# Core.net
KiCad netlist of a schematic drawn in Altium Designer
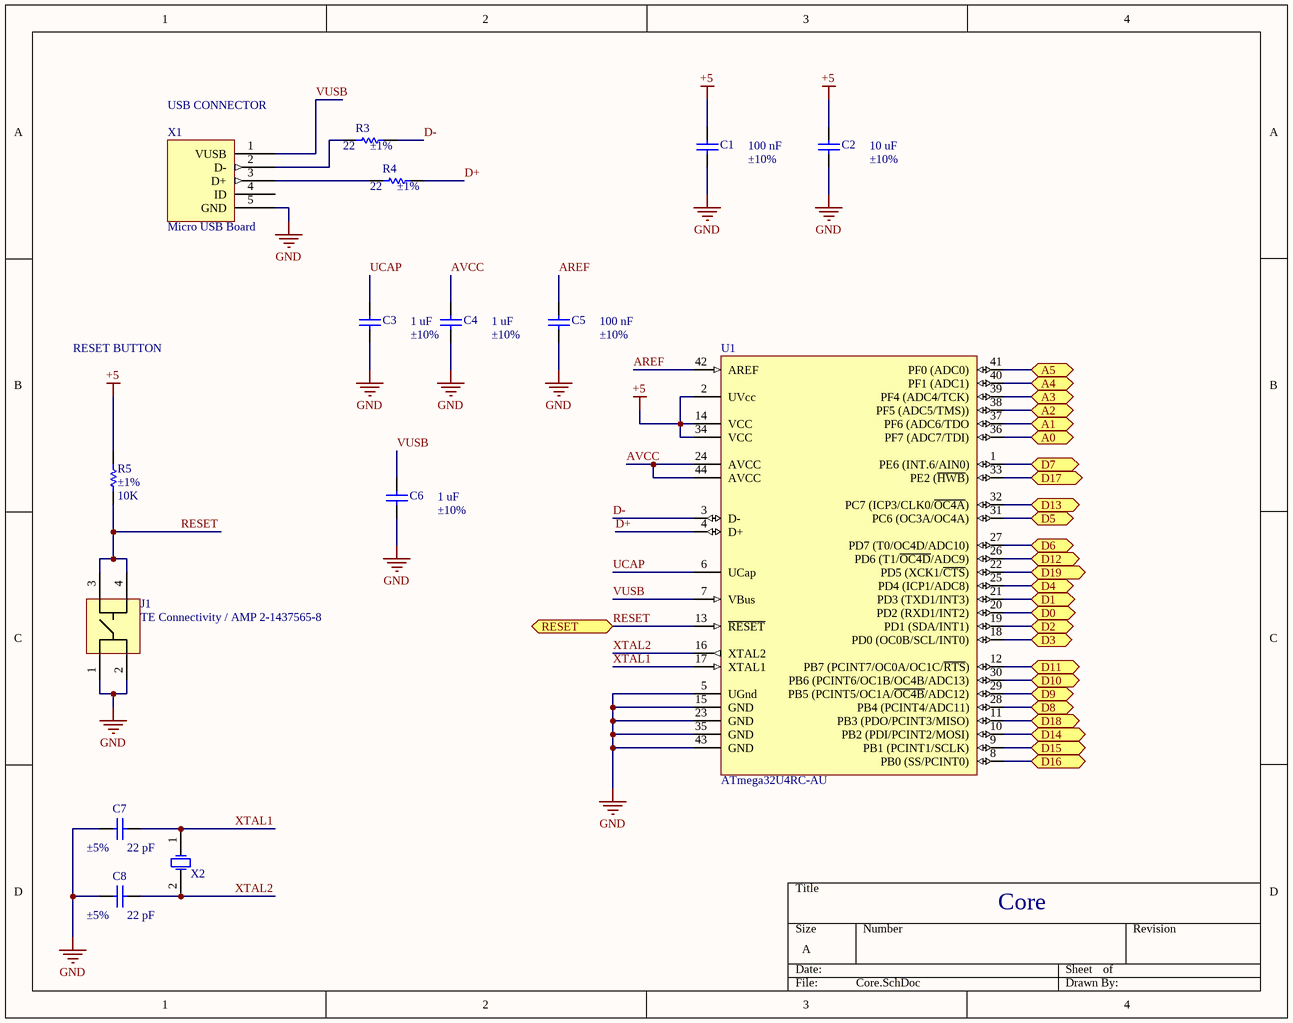
[diagram p0: Core.SchDoc]

(export (version "E")
  (design (tool "Eeschema 10.0.6"))
  (components
    (comp (ref "C1")
      (value "Taiyo Yuden LMK212BJ106KG-T")
      (footprint "PCB-i747o4qnz4fc2aqkwc14-1")
      (description "Cap Ceramic 10uF 10V X5R 10% SMD 0805 85?C T/R")
      (fields
        (field (name "MANUFACTURER PART NUMBER") "LMK212BJ106KG-T")
        (field (name "CAPACITANCE") "100 nF")
        (field (name "CAPACITANCE TOLERANCE") "±10%")
      )
      (libsource (lib "CommunityVault") (part "CMP-6ecba7c24c09b10c-2"))
    )
    (comp (ref "C2")
      (value "Taiyo Yuden LMK212BJ106KG-T")
      (footprint "PCB-i747o4qnz4fc2aqkwc14-1")
      (description "Cap Ceramic 10uF 10V X5R 10% SMD 0805 85?C T/R")
      (fields
        (field (name "MANUFACTURER PART NUMBER") "LMK212BJ106KG-T")
        (field (name "CAPACITANCE") "10 uF")
        (field (name "CAPACITANCE TOLERANCE") "±10%")
      )
      (libsource (lib "CommunityVault") (part "CMP-6ecba7c24c09b10c-2"))
    )
    (comp (ref "C3")
      (value "Taiyo Yuden LMK212BJ106KG-T")
      (footprint "PCB-i747o4qnz4fc2aqkwc14-1")
      (description "Cap Ceramic 10uF 10V X5R 10% SMD 0805 85?C T/R")
      (fields
        (field (name "MANUFACTURER PART NUMBER") "LMK212BJ106KG-T")
        (field (name "CAPACITANCE") "1 uF")
        (field (name "CAPACITANCE TOLERANCE") "±10%")
      )
      (libsource (lib "CommunityVault") (part "CMP-6ecba7c24c09b10c-2"))
    )
    (comp (ref "C4")
      (value "Taiyo Yuden LMK212BJ106KG-T")
      (footprint "PCB-i747o4qnz4fc2aqkwc14-1")
      (description "Cap Ceramic 10uF 10V X5R 10% SMD 0805 85?C T/R")
      (fields
        (field (name "MANUFACTURER PART NUMBER") "LMK212BJ106KG-T")
        (field (name "CAPACITANCE") "1 uF")
        (field (name "CAPACITANCE TOLERANCE") "±10%")
      )
      (libsource (lib "CommunityVault") (part "CMP-6ecba7c24c09b10c-2"))
    )
    (comp (ref "C5")
      (value "Taiyo Yuden LMK212BJ106KG-T")
      (footprint "PCB-i747o4qnz4fc2aqkwc14-1")
      (description "Cap Ceramic 10uF 10V X5R 10% SMD 0805 85?C T/R")
      (fields
        (field (name "MANUFACTURER PART NUMBER") "LMK212BJ106KG-T")
        (field (name "CAPACITANCE") "100 nF")
        (field (name "CAPACITANCE TOLERANCE") "±10%")
      )
      (libsource (lib "CommunityVault") (part "CMP-6ecba7c24c09b10c-2"))
    )
    (comp (ref "C6")
      (value "Taiyo Yuden LMK212BJ106KG-T")
      (footprint "PCB-i747o4qnz4fc2aqkwc14-1")
      (description "Cap Ceramic 10uF 10V X5R 10% SMD 0805 85?C T/R")
      (fields
        (field (name "MANUFACTURER PART NUMBER") "LMK212BJ106KG-T")
        (field (name "CAPACITANCE") "1 uF")
        (field (name "CAPACITANCE TOLERANCE") "±10%")
      )
      (libsource (lib "CommunityVault") (part "CMP-6ecba7c24c09b10c-2"))
    )
    (comp (ref "C7")
      (value "Taiyo Yuden LMK212BJ106KG-T")
      (footprint "PCB-i747o4qnz4fc2aqkwc14-1")
      (description "Cap Ceramic 10uF 10V X5R 10% SMD 0805 85?C T/R")
      (fields
        (field (name "MANUFACTURER PART NUMBER") "LMK212BJ106KG-T")
        (field (name "CAPACITANCE") "22 pF")
        (field (name "CAPACITANCE TOLERANCE") "±5%")
      )
      (libsource (lib "CommunityVault") (part "CMP-6ecba7c24c09b10c-2"))
    )
    (comp (ref "C8")
      (value "Taiyo Yuden LMK212BJ106KG-T")
      (footprint "PCB-i747o4qnz4fc2aqkwc14-1")
      (description "Cap Ceramic 10uF 10V X5R 10% SMD 0805 85?C T/R")
      (fields
        (field (name "MANUFACTURER PART NUMBER") "LMK212BJ106KG-T")
        (field (name "CAPACITANCE") "22 pF")
        (field (name "CAPACITANCE TOLERANCE") "±5%")
      )
      (libsource (lib "CommunityVault") (part "CMP-6ecba7c24c09b10c-2"))
    )
    (comp (ref "J1")
      (value "TE Connectivity / AMP 2-1437565-8")
      (footprint "PCB-70k6oqbhuv68f7gyhifn-1")
      (description "Switch Tactile OFF (ON) SPST Round Button Gull Wing 0.05A 12VDC 2.55N SMD Loose Piece")
      (fields (field (name "MANUFACTURER PART NUMBER") "2-1437565-8"))
      (libsource (lib "Octopart library") (part "SYM-fb7e300dae6a24b9-1"))
    )
    (comp (ref "R3")
      (value "Bourns CR0805-FX-4701GLF")
      (footprint "PCB-4097432-1")
      (description "Res Thick Film 0805 4.7K Ohm 1% 1/8W ±100ppm/°C Molded SMD SMD Paper Tape on Plastic Reel")
      (fields
        (field (name "MANUFACTURER PART NUMBER") "CR0805-FX-4701GLF")
        (field (name "RESISTANCE TOLERANCE") "±1%")
        (field (name "RESISTANCE") "22")
      )
      (libsource (lib "CommunityVault") (part "CMP-97505e06006c4897-1"))
    )
    (comp (ref "R4")
      (value "Bourns CR0805-FX-4701GLF")
      (footprint "PCB-4097432-1")
      (description "Res Thick Film 0805 4.7K Ohm 1% 1/8W ±100ppm/°C Molded SMD SMD Paper Tape on Plastic Reel")
      (fields
        (field (name "MANUFACTURER PART NUMBER") "CR0805-FX-4701GLF")
        (field (name "RESISTANCE TOLERANCE") "±1%")
        (field (name "RESISTANCE") "22")
      )
      (libsource (lib "CommunityVault") (part "CMP-97505e06006c4897-1"))
    )
    (comp (ref "R5")
      (value "Bourns CR0805-FX-4701GLF")
      (footprint "PCB-4097432-1")
      (description "Res Thick Film 0805 4.7K Ohm 1% 1/8W ±100ppm/°C Molded SMD SMD Paper Tape on Plastic Reel")
      (fields
        (field (name "MANUFACTURER PART NUMBER") "CR0805-FX-4701GLF")
        (field (name "RESISTANCE TOLERANCE") "±1%")
        (field (name "RESISTANCE") "10K")
      )
      (libsource (lib "CommunityVault") (part "CMP-97505e06006c4897-1"))
    )
    (comp (ref "U1")
      (value "ATmega32U4RC-AU")
      (footprint "44ML_L")
      (fields (field (name "MANUFACTURER") "Atmel"))
      (libsource (lib "Octopart library") (part "MC-8B-ATM16U4-SQ44"))
    )
    (comp (ref "X1")
      (value "Micro USB Board")
      (footprint "PCB-y0d6oczsv3eu57ue5a53-1")
      (libsource (lib "CommunityVault") (part "CMP-dryhiu0utvtqwfw1f267-2"))
    )
    (comp (ref "X2")
      (value "Fox Electronics FOXSDLF/160-20")
      (footprint "FOX-FOXSDLF-160-20")
      (description "CRYSTAL 16.0MHZ 20PF SMD")
      (libsource (lib "CommunityVault") (part "CMP-779572-4"))
    )
  )
  (nets
    (net (code "1") (name "+5") (class "Default")
      (node (ref "C1") (pin "2") (pinfunction "2_2") (pintype "passive"))
      (node (ref "C2") (pin "2") (pinfunction "2_2") (pintype "passive"))
      (node (ref "R5") (pin "2") (pinfunction "2_2") (pintype "passive"))
      (node (ref "U1") (pin "14") (pinfunction "VCC_14") (pintype "power_in"))
      (node (ref "U1") (pin "2") (pinfunction "UVcc_2") (pintype "power_in"))
      (node (ref "U1") (pin "34") (pinfunction "VCC_34") (pintype "power_in"))
    )
    (net (code "2") (name "/A0") (class "Default")
      (node (ref "U1") (pin "36") (pinfunction "PF7_(ADC7/TDI)_36") (pintype "bidirectional"))
    )
    (net (code "3") (name "/A1") (class "Default")
      (node (ref "U1") (pin "37") (pinfunction "PF6_(ADC6/TDO_37") (pintype "bidirectional"))
    )
    (net (code "4") (name "/A2") (class "Default")
      (node (ref "U1") (pin "38") (pinfunction "PF5_(ADC5/TMS))_38") (pintype "bidirectional"))
    )
    (net (code "5") (name "/A3") (class "Default")
      (node (ref "U1") (pin "39") (pinfunction "PF4_(ADC4/TCK)_39") (pintype "bidirectional"))
    )
    (net (code "6") (name "/A4") (class "Default")
      (node (ref "U1") (pin "40") (pinfunction "PF1_(ADC1)_40") (pintype "bidirectional"))
    )
    (net (code "7") (name "/A5") (class "Default")
      (node (ref "U1") (pin "41") (pinfunction "PF0_(ADC0)_41") (pintype "bidirectional"))
    )
    (net (code "8") (name "/AREF") (class "Default")
      (node (ref "C5") (pin "2") (pinfunction "2_2") (pintype "passive"))
      (node (ref "U1") (pin "42") (pinfunction "AREF_42") (pintype "input"))
    )
    (net (code "9") (name "/AVCC") (class "Default")
      (node (ref "C4") (pin "2") (pinfunction "2_2") (pintype "passive"))
      (node (ref "U1") (pin "24") (pinfunction "AVCC_24") (pintype "power_in"))
      (node (ref "U1") (pin "44") (pinfunction "AVCC_44") (pintype "power_in"))
    )
    (net (code "10") (name "/D+") (class "Default")
      (node (ref "R4") (pin "2") (pinfunction "2_2") (pintype "passive"))
      (node (ref "U1") (pin "4") (pinfunction "D+_4") (pintype "bidirectional"))
    )
    (net (code "11") (name "/D-") (class "Default")
      (node (ref "R3") (pin "2") (pinfunction "2_2") (pintype "passive"))
      (node (ref "U1") (pin "3") (pinfunction "D-_3") (pintype "bidirectional"))
    )
    (net (code "12") (name "/D0") (class "Default")
      (node (ref "U1") (pin "20") (pinfunction "PD2_(RXD1/INT2)_20") (pintype "bidirectional"))
    )
    (net (code "13") (name "/D1") (class "Default")
      (node (ref "U1") (pin "21") (pinfunction "PD3_(TXD1/INT3)_21") (pintype "bidirectional"))
    )
    (net (code "14") (name "/D2") (class "Default")
      (node (ref "U1") (pin "19") (pinfunction "PD1_(SDA/INT1)_19") (pintype "bidirectional"))
    )
    (net (code "15") (name "/D3") (class "Default")
      (node (ref "U1") (pin "18") (pinfunction "PD0_(OC0B/SCL/INT0)_18") (pintype "bidirectional"))
    )
    (net (code "16") (name "/D4") (class "Default")
      (node (ref "U1") (pin "25") (pinfunction "PD4_(ICP1/ADC8)_25") (pintype "bidirectional"))
    )
    (net (code "17") (name "/D5") (class "Default")
      (node (ref "U1") (pin "31") (pinfunction "PC6_(OC3A/OC4A)_31") (pintype "bidirectional"))
    )
    (net (code "18") (name "/D6") (class "Default")
      (node (ref "U1") (pin "27") (pinfunction "PD7_(T0/OC4D/ADC10)_27") (pintype "bidirectional"))
    )
    (net (code "19") (name "/D7") (class "Default")
      (node (ref "U1") (pin "1") (pinfunction "PE6_(INT.6/AIN0)_1") (pintype "bidirectional"))
    )
    (net (code "20") (name "/D8") (class "Default")
      (node (ref "U1") (pin "28") (pinfunction "PB4_(PCINT4/ADC11)_28") (pintype "bidirectional"))
    )
    (net (code "21") (name "/D9") (class "Default")
      (node (ref "U1") (pin "29") (pinfunction "PB5_(PCINT5/OC1A/~{OC4B}/ADC12)_29") (pintype "bidirectional"))
    )
    (net (code "22") (name "/D10") (class "Default")
      (node (ref "U1") (pin "30") (pinfunction "PB6_(PCINT6/OC1B/OC4B/ADC13)_30") (pintype "bidirectional"))
    )
    (net (code "23") (name "/D11") (class "Default")
      (node (ref "U1") (pin "12") (pinfunction "PB7_(PCINT7/OC0A/OC1C/~{RTS})_12") (pintype "bidirectional"))
    )
    (net (code "24") (name "/D12") (class "Default")
      (node (ref "U1") (pin "26") (pinfunction "PD6_(T1/~{OC4D}/ADC9)_26") (pintype "bidirectional"))
    )
    (net (code "25") (name "/D13") (class "Default")
      (node (ref "U1") (pin "32") (pinfunction "PC7_(ICP3/CLK0/~{OC4A})_32") (pintype "bidirectional"))
    )
    (net (code "26") (name "/D14") (class "Default")
      (node (ref "U1") (pin "10") (pinfunction "PB2_(PDI/PCINT2/MOSI)_10") (pintype "bidirectional"))
    )
    (net (code "27") (name "/D15") (class "Default")
      (node (ref "U1") (pin "9") (pinfunction "PB1_(PCINT1/SCLK)_9") (pintype "bidirectional"))
    )
    (net (code "28") (name "/D16") (class "Default")
      (node (ref "U1") (pin "8") (pinfunction "PB0_(SS/PCINT0)_8") (pintype "bidirectional"))
    )
    (net (code "29") (name "/D17") (class "Default")
      (node (ref "U1") (pin "33") (pinfunction "PE2_(~{HWB})_33") (pintype "bidirectional"))
    )
    (net (code "30") (name "/D18") (class "Default")
      (node (ref "U1") (pin "11") (pinfunction "PB3_(PDO/PCINT3/MISO)_11") (pintype "bidirectional"))
    )
    (net (code "31") (name "/D19") (class "Default")
      (node (ref "U1") (pin "22") (pinfunction "PD5_(XCK1/~{CTS})_22") (pintype "bidirectional"))
    )
    (net (code "32") (name "/RESET") (class "Default")
      (node (ref "J1") (pin "3") (pinfunction "3_3") (pintype "passive"))
      (node (ref "J1") (pin "4") (pinfunction "4_4") (pintype "passive"))
      (node (ref "R5") (pin "1") (pinfunction "1_1") (pintype "passive"))
      (node (ref "U1") (pin "13") (pinfunction "~{RESET}_13") (pintype "input"))
    )
    (net (code "33") (name "/UCAP") (class "Default")
      (node (ref "C3") (pin "2") (pinfunction "2_2") (pintype "passive"))
      (node (ref "U1") (pin "6") (pinfunction "UCap_6") (pintype "passive"))
    )
    (net (code "34") (name "/VUSB") (class "Default")
      (node (ref "C6") (pin "2") (pinfunction "2_2") (pintype "passive"))
      (node (ref "U1") (pin "7") (pinfunction "VBus_7") (pintype "input"))
      (node (ref "X1") (pin "1") (pinfunction "VUSB_1") (pintype "power_in"))
    )
    (net (code "35") (name "/XTAL1") (class "Default")
      (node (ref "C7") (pin "2") (pinfunction "2_2") (pintype "passive"))
      (node (ref "U1") (pin "17") (pinfunction "XTAL1_17") (pintype "input"))
      (node (ref "X2") (pin "1") (pinfunction "OSC1_1") (pintype "passive"))
    )
    (net (code "36") (name "/XTAL2") (class "Default")
      (node (ref "C8") (pin "2") (pinfunction "2_2") (pintype "passive"))
      (node (ref "U1") (pin "16") (pinfunction "XTAL2_16") (pintype "output"))
      (node (ref "X2") (pin "2") (pinfunction "OSC2_2") (pintype "passive"))
    )
    (net (code "37") (name "GND") (class "Default")
      (node (ref "C1") (pin "1") (pinfunction "1_1") (pintype "passive"))
      (node (ref "C2") (pin "1") (pinfunction "1_1") (pintype "passive"))
      (node (ref "C3") (pin "1") (pinfunction "1_1") (pintype "passive"))
      (node (ref "C4") (pin "1") (pinfunction "1_1") (pintype "passive"))
      (node (ref "C5") (pin "1") (pinfunction "1_1") (pintype "passive"))
      (node (ref "C6") (pin "1") (pinfunction "1_1") (pintype "passive"))
      (node (ref "C7") (pin "1") (pinfunction "1_1") (pintype "passive"))
      (node (ref "C8") (pin "1") (pinfunction "1_1") (pintype "passive"))
      (node (ref "J1") (pin "1") (pinfunction "1_1") (pintype "passive"))
      (node (ref "J1") (pin "2") (pinfunction "2_2") (pintype "passive"))
      (node (ref "U1") (pin "15") (pinfunction "GND_15") (pintype "power_in"))
      (node (ref "U1") (pin "23") (pinfunction "GND_23") (pintype "power_in"))
      (node (ref "U1") (pin "35") (pinfunction "GND_35") (pintype "power_in"))
      (node (ref "U1") (pin "43") (pinfunction "GND_43") (pintype "power_in"))
      (node (ref "U1") (pin "5") (pinfunction "UGnd_5") (pintype "power_in"))
      (node (ref "X1") (pin "5") (pinfunction "GND_5") (pintype "power_in"))
    )
    (net (code "38") (name "Net-(X1-D+)") (class "Default")
      (node (ref "R4") (pin "1") (pinfunction "1_1") (pintype "passive"))
      (node (ref "X1") (pin "3") (pinfunction "D+_3") (pintype "output"))
    )
    (net (code "39") (name "Net-(X1-D-)") (class "Default")
      (node (ref "R3") (pin "1") (pinfunction "1_1") (pintype "passive"))
      (node (ref "X1") (pin "2") (pinfunction "D-_2") (pintype "output"))
    )
    (net (code "40") (name "unconnected-(X1-ID-Pad4)") (class "Default")
      (node (ref "X1") (pin "4") (pinfunction "ID_4") (pintype "passive"))
    )
  )
)
